# WL-CPU.net
KiCad netlist of a schematic drawn in Altium Designer
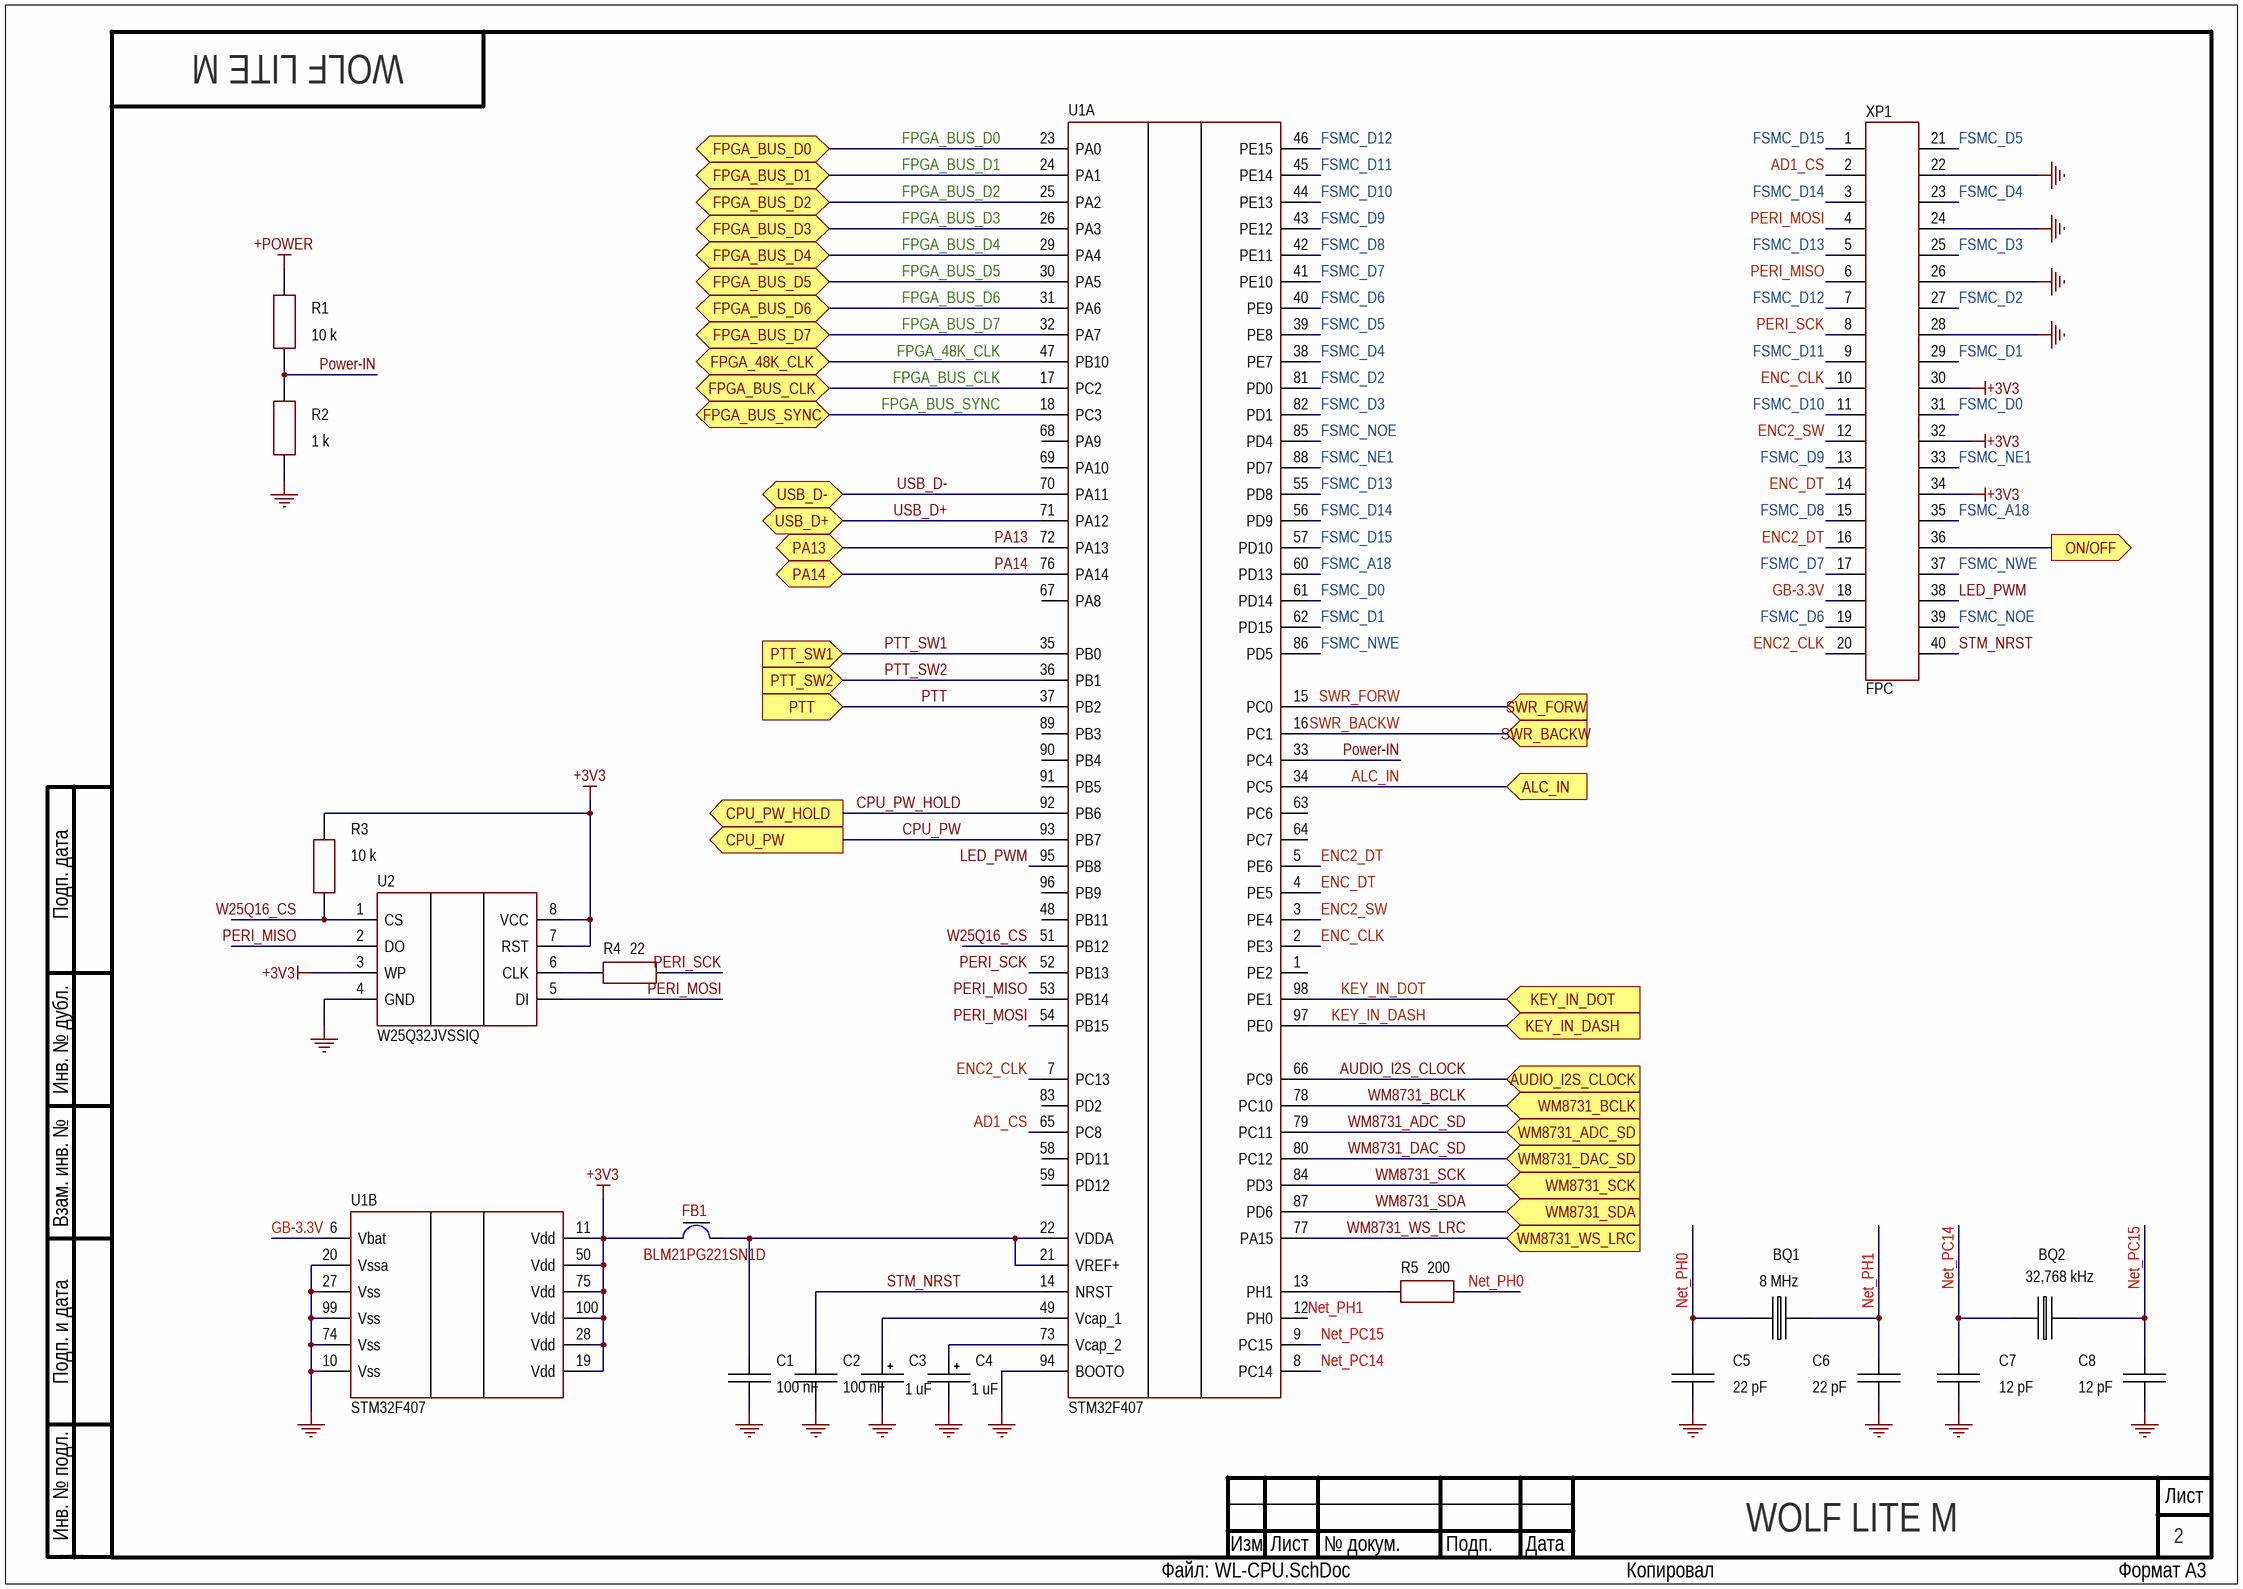
[diagram p0: WL-CPU.SchDoc]

(export (version "E")
  (design (tool "Eeschema 10.0.6"))
  (components
    (comp (ref "BQ1")
      (value "8 MHz")
      (footprint "SMD-4-CRYSTAL")
      (fields (field (name "PART NUMBER") "ABM3B-8.000MHZ-B2-T") (field (name "MANUFACTURER") "Abracon LLC"))
      (libsource (lib "GOST") (part "Resonator-1-4"))
    )
    (comp (ref "BQ2")
      (value "32,768 kHz")
      (footprint "SOJ-4")
      (fields (field (name "PART NUMBER") "ABS25-32.768KHZ-T") (field (name "MANUFACTURER") "Abracon LLC"))
      (libsource (lib "GOST") (part "Resonator-1-4"))
    )
    (comp (ref "C1")
      (value "100 nF")
      (footprint "C-0805-0.95")
      (fields
        (field (name "MANUFACTURER") "Yageo")
        (field (name "PART NUMBER") "CC0805KRX7R9BB104")
        (field (name "TOLERANCE") "±10%")
      )
      (libsource (lib "GOST") (part "Capacitor"))
    )
    (comp (ref "C2")
      (value "100 nF")
      (footprint "C-0805-0.95")
      (fields
        (field (name "MANUFACTURER") "Yageo")
        (field (name "PART NUMBER") "CC0805KRX7R9BB104")
        (field (name "TOLERANCE") "±10%")
      )
      (libsource (lib "GOST") (part "Capacitor"))
    )
    (comp (ref "C3")
      (value "1 uF")
      (footprint "CAP-CASE B")
      (fields
        (field (name "MANUFACTURER") "Panasonic Electronic Components")
        (field (name "PART NUMBER") "EEE-1HA010SR")
        (field (name "TOLERANCE") "±20%")
      )
      (libsource (lib "GOST") (part "Capacitor Polar"))
    )
    (comp (ref "C4")
      (value "1 uF")
      (footprint "CAP-CASE B")
      (fields
        (field (name "MANUFACTURER") "Panasonic Electronic Components")
        (field (name "PART NUMBER") "EEE-1HA010SR")
        (field (name "TOLERANCE") "±20%")
      )
      (libsource (lib "GOST") (part "Capacitor Polar"))
    )
    (comp (ref "C5")
      (value "22 pF")
      (footprint "C-0805-0.7")
      (fields
        (field (name "MANUFACTURER") "Yageo")
        (field (name "PART NUMBER") "CC0805JRNPO9BN220")
        (field (name "TOLERANCE") "±5%")
      )
      (libsource (lib "GOST") (part "Capacitor"))
    )
    (comp (ref "C6")
      (value "22 pF")
      (footprint "C-0805-0.7")
      (fields
        (field (name "MANUFACTURER") "Yageo")
        (field (name "PART NUMBER") "CC0805JRNPO9BN220")
        (field (name "TOLERANCE") "±5%")
      )
      (libsource (lib "GOST") (part "Capacitor"))
    )
    (comp (ref "C7")
      (value "12 pF")
      (footprint "C-0805-0.7")
      (fields
        (field (name "MANUFACTURER") "Yageo")
        (field (name "PART NUMBER") "CC0805JRNPO9BN120")
        (field (name "TOLERANCE") "±5%")
      )
      (libsource (lib "GOST") (part "Capacitor"))
    )
    (comp (ref "C8")
      (value "12 pF")
      (footprint "C-0805-0.7")
      (fields
        (field (name "MANUFACTURER") "Yageo")
        (field (name "PART NUMBER") "CC0805JRNPO9BN120")
        (field (name "TOLERANCE") "±5%")
      )
      (libsource (lib "GOST") (part "Capacitor"))
    )
    (comp (ref "FB1")
      (value "BLM21PG221SN1D")
      (footprint "L-0805")
      (fields (field (name "MANUFACTURER") "Murata Electronics"))
      (libsource (lib "GOST") (part "Ferrite Bead"))
    )
    (comp (ref "R1")
      (value "10 k")
      (footprint "R-0805")
      (fields
        (field (name "MANUFACTURER") "Yageo")
        (field (name "PART NUMBER") "RC0805JR-0710KL")
        (field (name "POWER") "0,125 W")
      )
      (libsource (lib "GOST") (part "Resistor"))
    )
    (comp (ref "R2")
      (value "1 k")
      (footprint "R-0805")
      (fields
        (field (name "MANUFACTURER") "Yageo")
        (field (name "PART NUMBER") "RC0805JR-071KL")
        (field (name "POWER") "0,125 W")
      )
      (libsource (lib "GOST") (part "Resistor"))
    )
    (comp (ref "R3")
      (value "10 k")
      (footprint "R-0805")
      (fields
        (field (name "MANUFACTURER") "Yageo")
        (field (name "PART NUMBER") "RC0805JR-0710KL")
        (field (name "POWER") "0,125 W")
      )
      (libsource (lib "GOST") (part "Resistor"))
    )
    (comp (ref "R4")
      (value "22")
      (footprint "R-0805")
      (fields
        (field (name "MANUFACTURER") "Yageo")
        (field (name "PART NUMBER") "RC0805JR-0722RL")
        (field (name "POWER") "0,125 W")
      )
      (libsource (lib "") (part "Resistor_1"))
    )
    (comp (ref "R5")
      (value "200")
      (footprint "R-0805")
      (fields
        (field (name "MANUFACTURER") "Yageo")
        (field (name "PART NUMBER") "RC0805JR-07200RL")
        (field (name "POWER") "0,125 W")
      )
      (libsource (lib "") (part "Resistor_2"))
    )
    (comp (ref "U1")
      (value "STM32F407")
      (footprint "LQFP-100")
      (fields (field (name "PART NUMBER") "STM32F407VGT6") (field (name "MANUFACTURER") "STMicroelectronics"))
      (libsource (lib "GOST") (part "STM32F407VGT6"))
    )
    (comp (ref "U2")
      (value "W25Q32JVSSIQ")
      (footprint "SOIC-8-W")
      (description "IC FLASH 32MBIT SPI/QUAD")
      (fields (field (name "MANUFACTURER") "Winbond Electronics"))
      (libsource (lib "GOST") (part "W25Q32JVSSIQ"))
    )
    (comp (ref "XP1")
      (value "FPC")
      (footprint "FPC-40-05-V")
      (fields (field (name "PART NUMBER") "AFC11-S40ICC-00") (field (name "MANUFACTURER") "JUSHUO"))
      (libsource (lib "GOST") (part "AFC11-S40ICC-00"))
    )
  )
  (nets
    (net (code "1") (name "+3V3") (class "Default")
      (node (ref "FB1") (pin "2") (pinfunction "2_2") (pintype "passive"))
      (node (ref "R3") (pin "2") (pinfunction "2_2") (pintype "passive"))
      (node (ref "U1") (pin "100") (pinfunction "Vdd_100") (pintype "passive"))
      (node (ref "U1") (pin "11") (pinfunction "Vdd_11") (pintype "passive"))
      (node (ref "U1") (pin "19") (pinfunction "Vdd_19") (pintype "passive"))
      (node (ref "U1") (pin "28") (pinfunction "Vdd_28") (pintype "passive"))
      (node (ref "U1") (pin "50") (pinfunction "Vdd_50") (pintype "passive"))
      (node (ref "U1") (pin "75") (pinfunction "Vdd_75") (pintype "passive"))
      (node (ref "U2") (pin "3") (pinfunction "WP_3") (pintype "passive"))
      (node (ref "U2") (pin "7") (pinfunction "RST_7") (pintype "passive"))
      (node (ref "U2") (pin "8") (pinfunction "VCC_8") (pintype "passive"))
      (node (ref "XP1") (pin "30") (pinfunction "30_30") (pintype "passive"))
      (node (ref "XP1") (pin "32") (pinfunction "32_32") (pintype "passive"))
      (node (ref "XP1") (pin "34") (pinfunction "34_34") (pintype "passive"))
    )
    (net (code "2") (name "+POWER") (class "Default")
      (node (ref "R1") (pin "2") (pinfunction "2_2") (pintype "passive"))
    )
    (net (code "3") (name "/AD1_CS") (class "Default")
      (node (ref "U1") (pin "65") (pinfunction "PC8_65") (pintype "passive"))
      (node (ref "XP1") (pin "2") (pinfunction "2_2") (pintype "passive"))
    )
    (net (code "4") (name "/ALC_IN") (class "Default")
      (node (ref "U1") (pin "34") (pinfunction "PC5_34") (pintype "passive"))
    )
    (net (code "5") (name "/AUDIO_I2S_CLOCK") (class "Default")
      (node (ref "U1") (pin "66") (pinfunction "PC9_66") (pintype "passive"))
    )
    (net (code "6") (name "/CPU_PW") (class "Default")
      (node (ref "U1") (pin "93") (pinfunction "PB7_93") (pintype "passive"))
    )
    (net (code "7") (name "/CPU_PW_HOLD") (class "Default")
      (node (ref "U1") (pin "92") (pinfunction "PB6_92") (pintype "passive"))
    )
    (net (code "8") (name "/ENC2_CLK") (class "Default")
      (node (ref "U1") (pin "7") (pinfunction "PC13_7") (pintype "passive"))
      (node (ref "XP1") (pin "20") (pinfunction "20_20") (pintype "passive"))
    )
    (net (code "9") (name "/ENC2_DT") (class "Default")
      (node (ref "U1") (pin "5") (pinfunction "PE6_5") (pintype "passive"))
      (node (ref "XP1") (pin "16") (pinfunction "16_16") (pintype "passive"))
    )
    (net (code "10") (name "/ENC2_SW") (class "Default")
      (node (ref "U1") (pin "3") (pinfunction "PE4_3") (pintype "passive"))
      (node (ref "XP1") (pin "12") (pinfunction "12_12") (pintype "passive"))
    )
    (net (code "11") (name "/ENC_CLK") (class "Default")
      (node (ref "U1") (pin "2") (pinfunction "PE3_2") (pintype "passive"))
      (node (ref "XP1") (pin "10") (pinfunction "10_10") (pintype "passive"))
    )
    (net (code "12") (name "/ENC_DT") (class "Default")
      (node (ref "U1") (pin "4") (pinfunction "PE5_4") (pintype "passive"))
      (node (ref "XP1") (pin "14") (pinfunction "14_14") (pintype "passive"))
    )
    (net (code "13") (name "/FPGA_48K_CLK") (class "Default")
      (node (ref "U1") (pin "47") (pinfunction "PB10_47") (pintype "passive"))
    )
    (net (code "14") (name "/FPGA_BUS_CLK") (class "Default")
      (node (ref "U1") (pin "17") (pinfunction "PC2_17") (pintype "passive"))
    )
    (net (code "15") (name "/FPGA_BUS_D0") (class "Default")
      (node (ref "U1") (pin "23") (pinfunction "PA0_23") (pintype "passive"))
    )
    (net (code "16") (name "/FPGA_BUS_D1") (class "Default")
      (node (ref "U1") (pin "24") (pinfunction "PA1_24") (pintype "passive"))
    )
    (net (code "17") (name "/FPGA_BUS_D2") (class "Default")
      (node (ref "U1") (pin "25") (pinfunction "PA2_25") (pintype "passive"))
    )
    (net (code "18") (name "/FPGA_BUS_D3") (class "Default")
      (node (ref "U1") (pin "26") (pinfunction "PA3_26") (pintype "passive"))
    )
    (net (code "19") (name "/FPGA_BUS_D4") (class "Default")
      (node (ref "U1") (pin "29") (pinfunction "PA4_29") (pintype "passive"))
    )
    (net (code "20") (name "/FPGA_BUS_D5") (class "Default")
      (node (ref "U1") (pin "30") (pinfunction "PA5_30") (pintype "passive"))
    )
    (net (code "21") (name "/FPGA_BUS_D6") (class "Default")
      (node (ref "U1") (pin "31") (pinfunction "PA6_31") (pintype "passive"))
    )
    (net (code "22") (name "/FPGA_BUS_D7") (class "Default")
      (node (ref "U1") (pin "32") (pinfunction "PA7_32") (pintype "passive"))
    )
    (net (code "23") (name "/FPGA_BUS_SYNC") (class "Default")
      (node (ref "U1") (pin "18") (pinfunction "PC3_18") (pintype "passive"))
    )
    (net (code "24") (name "/FSMC_A18") (class "Default")
      (node (ref "U1") (pin "60") (pinfunction "PD13_60") (pintype "passive"))
      (node (ref "XP1") (pin "35") (pinfunction "35_35") (pintype "passive"))
    )
    (net (code "25") (name "/FSMC_D0") (class "Default")
      (node (ref "U1") (pin "61") (pinfunction "PD14_61") (pintype "passive"))
      (node (ref "XP1") (pin "31") (pinfunction "31_31") (pintype "passive"))
    )
    (net (code "26") (name "/FSMC_D1") (class "Default")
      (node (ref "U1") (pin "62") (pinfunction "PD15_62") (pintype "passive"))
      (node (ref "XP1") (pin "29") (pinfunction "29_29") (pintype "passive"))
    )
    (net (code "27") (name "/FSMC_D2") (class "Default")
      (node (ref "U1") (pin "81") (pinfunction "PD0_81") (pintype "passive"))
      (node (ref "XP1") (pin "27") (pinfunction "27_27") (pintype "passive"))
    )
    (net (code "28") (name "/FSMC_D3") (class "Default")
      (node (ref "U1") (pin "82") (pinfunction "PD1_82") (pintype "passive"))
      (node (ref "XP1") (pin "25") (pinfunction "25_25") (pintype "passive"))
    )
    (net (code "29") (name "/FSMC_D4") (class "Default")
      (node (ref "U1") (pin "38") (pinfunction "PE7_38") (pintype "passive"))
      (node (ref "XP1") (pin "23") (pinfunction "23_23") (pintype "passive"))
    )
    (net (code "30") (name "/FSMC_D5") (class "Default")
      (node (ref "U1") (pin "39") (pinfunction "PE8_39") (pintype "passive"))
      (node (ref "XP1") (pin "21") (pinfunction "21_21") (pintype "passive"))
    )
    (net (code "31") (name "/FSMC_D6") (class "Default")
      (node (ref "U1") (pin "40") (pinfunction "PE9_40") (pintype "passive"))
      (node (ref "XP1") (pin "19") (pinfunction "19_19") (pintype "passive"))
    )
    (net (code "32") (name "/FSMC_D7") (class "Default")
      (node (ref "U1") (pin "41") (pinfunction "PE10_41") (pintype "passive"))
      (node (ref "XP1") (pin "17") (pinfunction "17_17") (pintype "passive"))
    )
    (net (code "33") (name "/FSMC_D8") (class "Default")
      (node (ref "U1") (pin "42") (pinfunction "PE11_42") (pintype "passive"))
      (node (ref "XP1") (pin "15") (pinfunction "15_15") (pintype "passive"))
    )
    (net (code "34") (name "/FSMC_D9") (class "Default")
      (node (ref "U1") (pin "43") (pinfunction "PE12_43") (pintype "passive"))
      (node (ref "XP1") (pin "13") (pinfunction "13_13") (pintype "passive"))
    )
    (net (code "35") (name "/FSMC_D10") (class "Default")
      (node (ref "U1") (pin "44") (pinfunction "PE13_44") (pintype "passive"))
      (node (ref "XP1") (pin "11") (pinfunction "11_11") (pintype "passive"))
    )
    (net (code "36") (name "/FSMC_D11") (class "Default")
      (node (ref "U1") (pin "45") (pinfunction "PE14_45") (pintype "passive"))
      (node (ref "XP1") (pin "9") (pinfunction "9_9") (pintype "passive"))
    )
    (net (code "37") (name "/FSMC_D12") (class "Default")
      (node (ref "U1") (pin "46") (pinfunction "PE15_46") (pintype "passive"))
      (node (ref "XP1") (pin "7") (pinfunction "7_7") (pintype "passive"))
    )
    (net (code "38") (name "/FSMC_D13") (class "Default")
      (node (ref "U1") (pin "55") (pinfunction "PD8_55") (pintype "passive"))
      (node (ref "XP1") (pin "5") (pinfunction "5_5") (pintype "passive"))
    )
    (net (code "39") (name "/FSMC_D14") (class "Default")
      (node (ref "U1") (pin "56") (pinfunction "PD9_56") (pintype "passive"))
      (node (ref "XP1") (pin "3") (pinfunction "3_3") (pintype "passive"))
    )
    (net (code "40") (name "/FSMC_D15") (class "Default")
      (node (ref "U1") (pin "57") (pinfunction "PD10_57") (pintype "passive"))
      (node (ref "XP1") (pin "1") (pinfunction "1_1") (pintype "passive"))
    )
    (net (code "41") (name "/FSMC_NE1") (class "Default")
      (node (ref "U1") (pin "88") (pinfunction "PD7_88") (pintype "passive"))
      (node (ref "XP1") (pin "33") (pinfunction "33_33") (pintype "passive"))
    )
    (net (code "42") (name "/FSMC_NOE") (class "Default")
      (node (ref "U1") (pin "85") (pinfunction "PD4_85") (pintype "passive"))
      (node (ref "XP1") (pin "39") (pinfunction "39_39") (pintype "passive"))
    )
    (net (code "43") (name "/FSMC_NWE") (class "Default")
      (node (ref "U1") (pin "86") (pinfunction "PD5_86") (pintype "passive"))
      (node (ref "XP1") (pin "37") (pinfunction "37_37") (pintype "passive"))
    )
    (net (code "44") (name "/GB-3.3V") (class "Default")
      (node (ref "U1") (pin "6") (pinfunction "Vbat_6") (pintype "passive"))
      (node (ref "XP1") (pin "18") (pinfunction "18_18") (pintype "passive"))
    )
    (net (code "45") (name "/KEY_IN_DASH") (class "Default")
      (node (ref "U1") (pin "97") (pinfunction "PE0_97") (pintype "passive"))
    )
    (net (code "46") (name "/KEY_IN_DOT") (class "Default")
      (node (ref "U1") (pin "98") (pinfunction "PE1_98") (pintype "passive"))
    )
    (net (code "47") (name "/LED_PWM") (class "Default")
      (node (ref "U1") (pin "95") (pinfunction "PB8_95") (pintype "passive"))
      (node (ref "XP1") (pin "38") (pinfunction "38_38") (pintype "passive"))
    )
    (net (code "48") (name "/Net_PC14") (class "Default")
      (node (ref "BQ2") (pin "1") (pinfunction "1_1") (pintype "passive"))
      (node (ref "C7") (pin "2") (pinfunction "2_2") (pintype "passive"))
      (node (ref "U1") (pin "8") (pinfunction "PC14_8") (pintype "passive"))
    )
    (net (code "49") (name "/Net_PC15") (class "Default")
      (node (ref "BQ2") (pin "4") (pinfunction "4_4") (pintype "passive"))
      (node (ref "C8") (pin "2") (pinfunction "2_2") (pintype "passive"))
      (node (ref "U1") (pin "9") (pinfunction "PC15_9") (pintype "passive"))
    )
    (net (code "50") (name "/Net_PH0") (class "Default")
      (node (ref "BQ1") (pin "1") (pinfunction "1_1") (pintype "passive"))
      (node (ref "C5") (pin "2") (pinfunction "2_2") (pintype "passive"))
      (node (ref "R5") (pin "1") (pinfunction "1_1") (pintype "passive"))
    )
    (net (code "51") (name "/Net_PH1") (class "Default")
      (node (ref "BQ1") (pin "4") (pinfunction "4_4") (pintype "passive"))
      (node (ref "C6") (pin "2") (pinfunction "2_2") (pintype "passive"))
      (node (ref "U1") (pin "12") (pinfunction "PH0_12") (pintype "passive"))
    )
    (net (code "52") (name "/ON{slash}OFF") (class "Default")
      (node (ref "XP1") (pin "36") (pinfunction "36_36") (pintype "passive"))
    )
    (net (code "53") (name "/PA13") (class "Default")
      (node (ref "U1") (pin "72") (pinfunction "PA13_72") (pintype "passive"))
    )
    (net (code "54") (name "/PA14") (class "Default")
      (node (ref "U1") (pin "76") (pinfunction "PA14_76") (pintype "passive"))
    )
    (net (code "55") (name "/PERI_MISO") (class "Default")
      (node (ref "U1") (pin "53") (pinfunction "PB14_53") (pintype "passive"))
      (node (ref "U2") (pin "2") (pinfunction "DO_2") (pintype "passive"))
      (node (ref "XP1") (pin "6") (pinfunction "6_6") (pintype "passive"))
    )
    (net (code "56") (name "/PERI_MOSI") (class "Default")
      (node (ref "U1") (pin "54") (pinfunction "PB15_54") (pintype "passive"))
      (node (ref "U2") (pin "5") (pinfunction "DI_5") (pintype "passive"))
      (node (ref "XP1") (pin "4") (pinfunction "4_4") (pintype "passive"))
    )
    (net (code "57") (name "/PERI_SCK") (class "Default")
      (node (ref "R4") (pin "2") (pinfunction "2_2") (pintype "passive"))
      (node (ref "U1") (pin "52") (pinfunction "PB13_52") (pintype "passive"))
      (node (ref "XP1") (pin "8") (pinfunction "8_8") (pintype "passive"))
    )
    (net (code "58") (name "/PTT") (class "Default")
      (node (ref "U1") (pin "37") (pinfunction "PB2_37") (pintype "passive"))
    )
    (net (code "59") (name "/PTT_SW1") (class "Default")
      (node (ref "U1") (pin "35") (pinfunction "PB0_35") (pintype "passive"))
    )
    (net (code "60") (name "/PTT_SW2") (class "Default")
      (node (ref "U1") (pin "36") (pinfunction "PB1_36") (pintype "passive"))
    )
    (net (code "61") (name "/Power-IN") (class "Default")
      (node (ref "R1") (pin "1") (pinfunction "1_1") (pintype "passive"))
      (node (ref "R2") (pin "2") (pinfunction "2_2") (pintype "passive"))
      (node (ref "U1") (pin "33") (pinfunction "PC4_33") (pintype "passive"))
    )
    (net (code "62") (name "/STM_NRST") (class "Default")
      (node (ref "C2") (pin "2") (pinfunction "2_2") (pintype "passive"))
      (node (ref "U1") (pin "14") (pinfunction "NRST_14") (pintype "passive"))
      (node (ref "XP1") (pin "40") (pinfunction "40_40") (pintype "passive"))
    )
    (net (code "63") (name "/SWR_BACKW") (class "Default")
      (node (ref "U1") (pin "16") (pinfunction "PC1_16") (pintype "passive"))
    )
    (net (code "64") (name "/SWR_FORW") (class "Default")
      (node (ref "U1") (pin "15") (pinfunction "PC0_15") (pintype "passive"))
    )
    (net (code "65") (name "/USB_D+") (class "Default")
      (node (ref "U1") (pin "71") (pinfunction "PA12_71") (pintype "passive"))
    )
    (net (code "66") (name "/USB_D-") (class "Default")
      (node (ref "U1") (pin "70") (pinfunction "PA11_70") (pintype "passive"))
    )
    (net (code "67") (name "/W25Q16_CS") (class "Default")
      (node (ref "R3") (pin "1") (pinfunction "1_1") (pintype "passive"))
      (node (ref "U1") (pin "51") (pinfunction "PB12_51") (pintype "passive"))
      (node (ref "U2") (pin "1") (pinfunction "CS_1") (pintype "passive"))
    )
    (net (code "68") (name "/WM8731_ADC_SD") (class "Default")
      (node (ref "U1") (pin "79") (pinfunction "PC11_79") (pintype "passive"))
    )
    (net (code "69") (name "/WM8731_BCLK") (class "Default")
      (node (ref "U1") (pin "78") (pinfunction "PC10_78") (pintype "passive"))
    )
    (net (code "70") (name "/WM8731_DAC_SD") (class "Default")
      (node (ref "U1") (pin "80") (pinfunction "PC12_80") (pintype "passive"))
    )
    (net (code "71") (name "/WM8731_SCK") (class "Default")
      (node (ref "U1") (pin "84") (pinfunction "PD3_84") (pintype "passive"))
    )
    (net (code "72") (name "/WM8731_SDA") (class "Default")
      (node (ref "U1") (pin "87") (pinfunction "PD6_87") (pintype "passive"))
    )
    (net (code "73") (name "/WM8731_WS_LRC") (class "Default")
      (node (ref "U1") (pin "77") (pinfunction "PA15_77") (pintype "passive"))
    )
    (net (code "74") (name "GND") (class "Default")
      (node (ref "C1") (pin "2") (pinfunction "2_2") (pintype "passive"))
      (node (ref "C2") (pin "1") (pinfunction "1_1") (pintype "passive"))
      (node (ref "C3") (pin "2") (pinfunction "2_2") (pintype "passive"))
      (node (ref "C4") (pin "2") (pinfunction "2_2") (pintype "passive"))
      (node (ref "C5") (pin "1") (pinfunction "1_1") (pintype "passive"))
      (node (ref "C6") (pin "1") (pinfunction "1_1") (pintype "passive"))
      (node (ref "C7") (pin "1") (pinfunction "1_1") (pintype "passive"))
      (node (ref "C8") (pin "1") (pinfunction "1_1") (pintype "passive"))
      (node (ref "R2") (pin "1") (pinfunction "1_1") (pintype "passive"))
      (node (ref "U1") (pin "10") (pinfunction "Vss_10") (pintype "passive"))
      (node (ref "U1") (pin "20") (pinfunction "Vssa_20") (pintype "passive"))
      (node (ref "U1") (pin "27") (pinfunction "Vss_27") (pintype "passive"))
      (node (ref "U1") (pin "74") (pinfunction "Vss_74") (pintype "passive"))
      (node (ref "U1") (pin "94") (pinfunction "BOOTO_94") (pintype "passive"))
      (node (ref "U1") (pin "99") (pinfunction "Vss_99") (pintype "passive"))
      (node (ref "U2") (pin "4") (pinfunction "GND_4") (pintype "passive"))
      (node (ref "XP1") (pin "22") (pinfunction "22_22") (pintype "passive"))
      (node (ref "XP1") (pin "24") (pinfunction "24_24") (pintype "passive"))
      (node (ref "XP1") (pin "26") (pinfunction "26_26") (pintype "passive"))
      (node (ref "XP1") (pin "28") (pinfunction "28_28") (pintype "passive"))
    )
    (net (code "75") (name "Net-(U1A-PH1)") (class "Default")
      (node (ref "R5") (pin "2") (pinfunction "2_2") (pintype "passive"))
      (node (ref "U1") (pin "13") (pinfunction "PH1_13") (pintype "passive"))
    )
    (net (code "76") (name "Net-(U1A-VDDA)") (class "Default")
      (node (ref "C1") (pin "1") (pinfunction "1_1") (pintype "passive"))
      (node (ref "FB1") (pin "1") (pinfunction "1_1") (pintype "passive"))
      (node (ref "U1") (pin "21") (pinfunction "VREF+_21") (pintype "passive"))
      (node (ref "U1") (pin "22") (pinfunction "VDDA_22") (pintype "passive"))
    )
    (net (code "77") (name "Net-(U1A-Vcap_1)") (class "Default")
      (node (ref "C3") (pin "1") (pinfunction "1_1") (pintype "passive"))
      (node (ref "U1") (pin "49") (pinfunction "Vcap_1_49") (pintype "passive"))
    )
    (net (code "78") (name "Net-(U1A-Vcap_2)") (class "Default")
      (node (ref "C4") (pin "1") (pinfunction "1_1") (pintype "passive"))
      (node (ref "U1") (pin "73") (pinfunction "Vcap_2_73") (pintype "passive"))
    )
    (net (code "79") (name "Net-(U2-CLK)") (class "Default")
      (node (ref "R4") (pin "1") (pinfunction "1_1") (pintype "passive"))
      (node (ref "U2") (pin "6") (pinfunction "CLK_6") (pintype "passive"))
    )
    (net (code "80") (name "unconnected-(U1A-PA8-Pad67)") (class "Default")
      (node (ref "U1") (pin "67") (pinfunction "PA8_67") (pintype "passive"))
    )
    (net (code "81") (name "unconnected-(U1A-PA9-Pad68)") (class "Default")
      (node (ref "U1") (pin "68") (pinfunction "PA9_68") (pintype "passive"))
    )
    (net (code "82") (name "unconnected-(U1A-PA10-Pad69)") (class "Default")
      (node (ref "U1") (pin "69") (pinfunction "PA10_69") (pintype "passive"))
    )
    (net (code "83") (name "unconnected-(U1A-PB3-Pad89)") (class "Default")
      (node (ref "U1") (pin "89") (pinfunction "PB3_89") (pintype "passive"))
    )
    (net (code "84") (name "unconnected-(U1A-PB4-Pad90)") (class "Default")
      (node (ref "U1") (pin "90") (pinfunction "PB4_90") (pintype "passive"))
    )
    (net (code "85") (name "unconnected-(U1A-PB5-Pad91)") (class "Default")
      (node (ref "U1") (pin "91") (pinfunction "PB5_91") (pintype "passive"))
    )
    (net (code "86") (name "unconnected-(U1A-PB9-Pad96)") (class "Default")
      (node (ref "U1") (pin "96") (pinfunction "PB9_96") (pintype "passive"))
    )
    (net (code "87") (name "unconnected-(U1A-PB11-Pad48)") (class "Default")
      (node (ref "U1") (pin "48") (pinfunction "PB11_48") (pintype "passive"))
    )
    (net (code "88") (name "unconnected-(U1A-PC6-Pad63)") (class "Default")
      (node (ref "U1") (pin "63") (pinfunction "PC6_63") (pintype "passive"))
    )
    (net (code "89") (name "unconnected-(U1A-PC7-Pad64)") (class "Default")
      (node (ref "U1") (pin "64") (pinfunction "PC7_64") (pintype "passive"))
    )
    (net (code "90") (name "unconnected-(U1A-PD2-Pad83)") (class "Default")
      (node (ref "U1") (pin "83") (pinfunction "PD2_83") (pintype "passive"))
    )
    (net (code "91") (name "unconnected-(U1A-PD11-Pad58)") (class "Default")
      (node (ref "U1") (pin "58") (pinfunction "PD11_58") (pintype "passive"))
    )
    (net (code "92") (name "unconnected-(U1A-PD12-Pad59)") (class "Default")
      (node (ref "U1") (pin "59") (pinfunction "PD12_59") (pintype "passive"))
    )
    (net (code "93") (name "unconnected-(U1A-PE2-Pad1)") (class "Default")
      (node (ref "U1") (pin "1") (pinfunction "PE2_1") (pintype "passive"))
    )
  )
)
